# 1____DI_DO___v1_0.net
KiCad netlist of a schematic drawn in Altium Designer
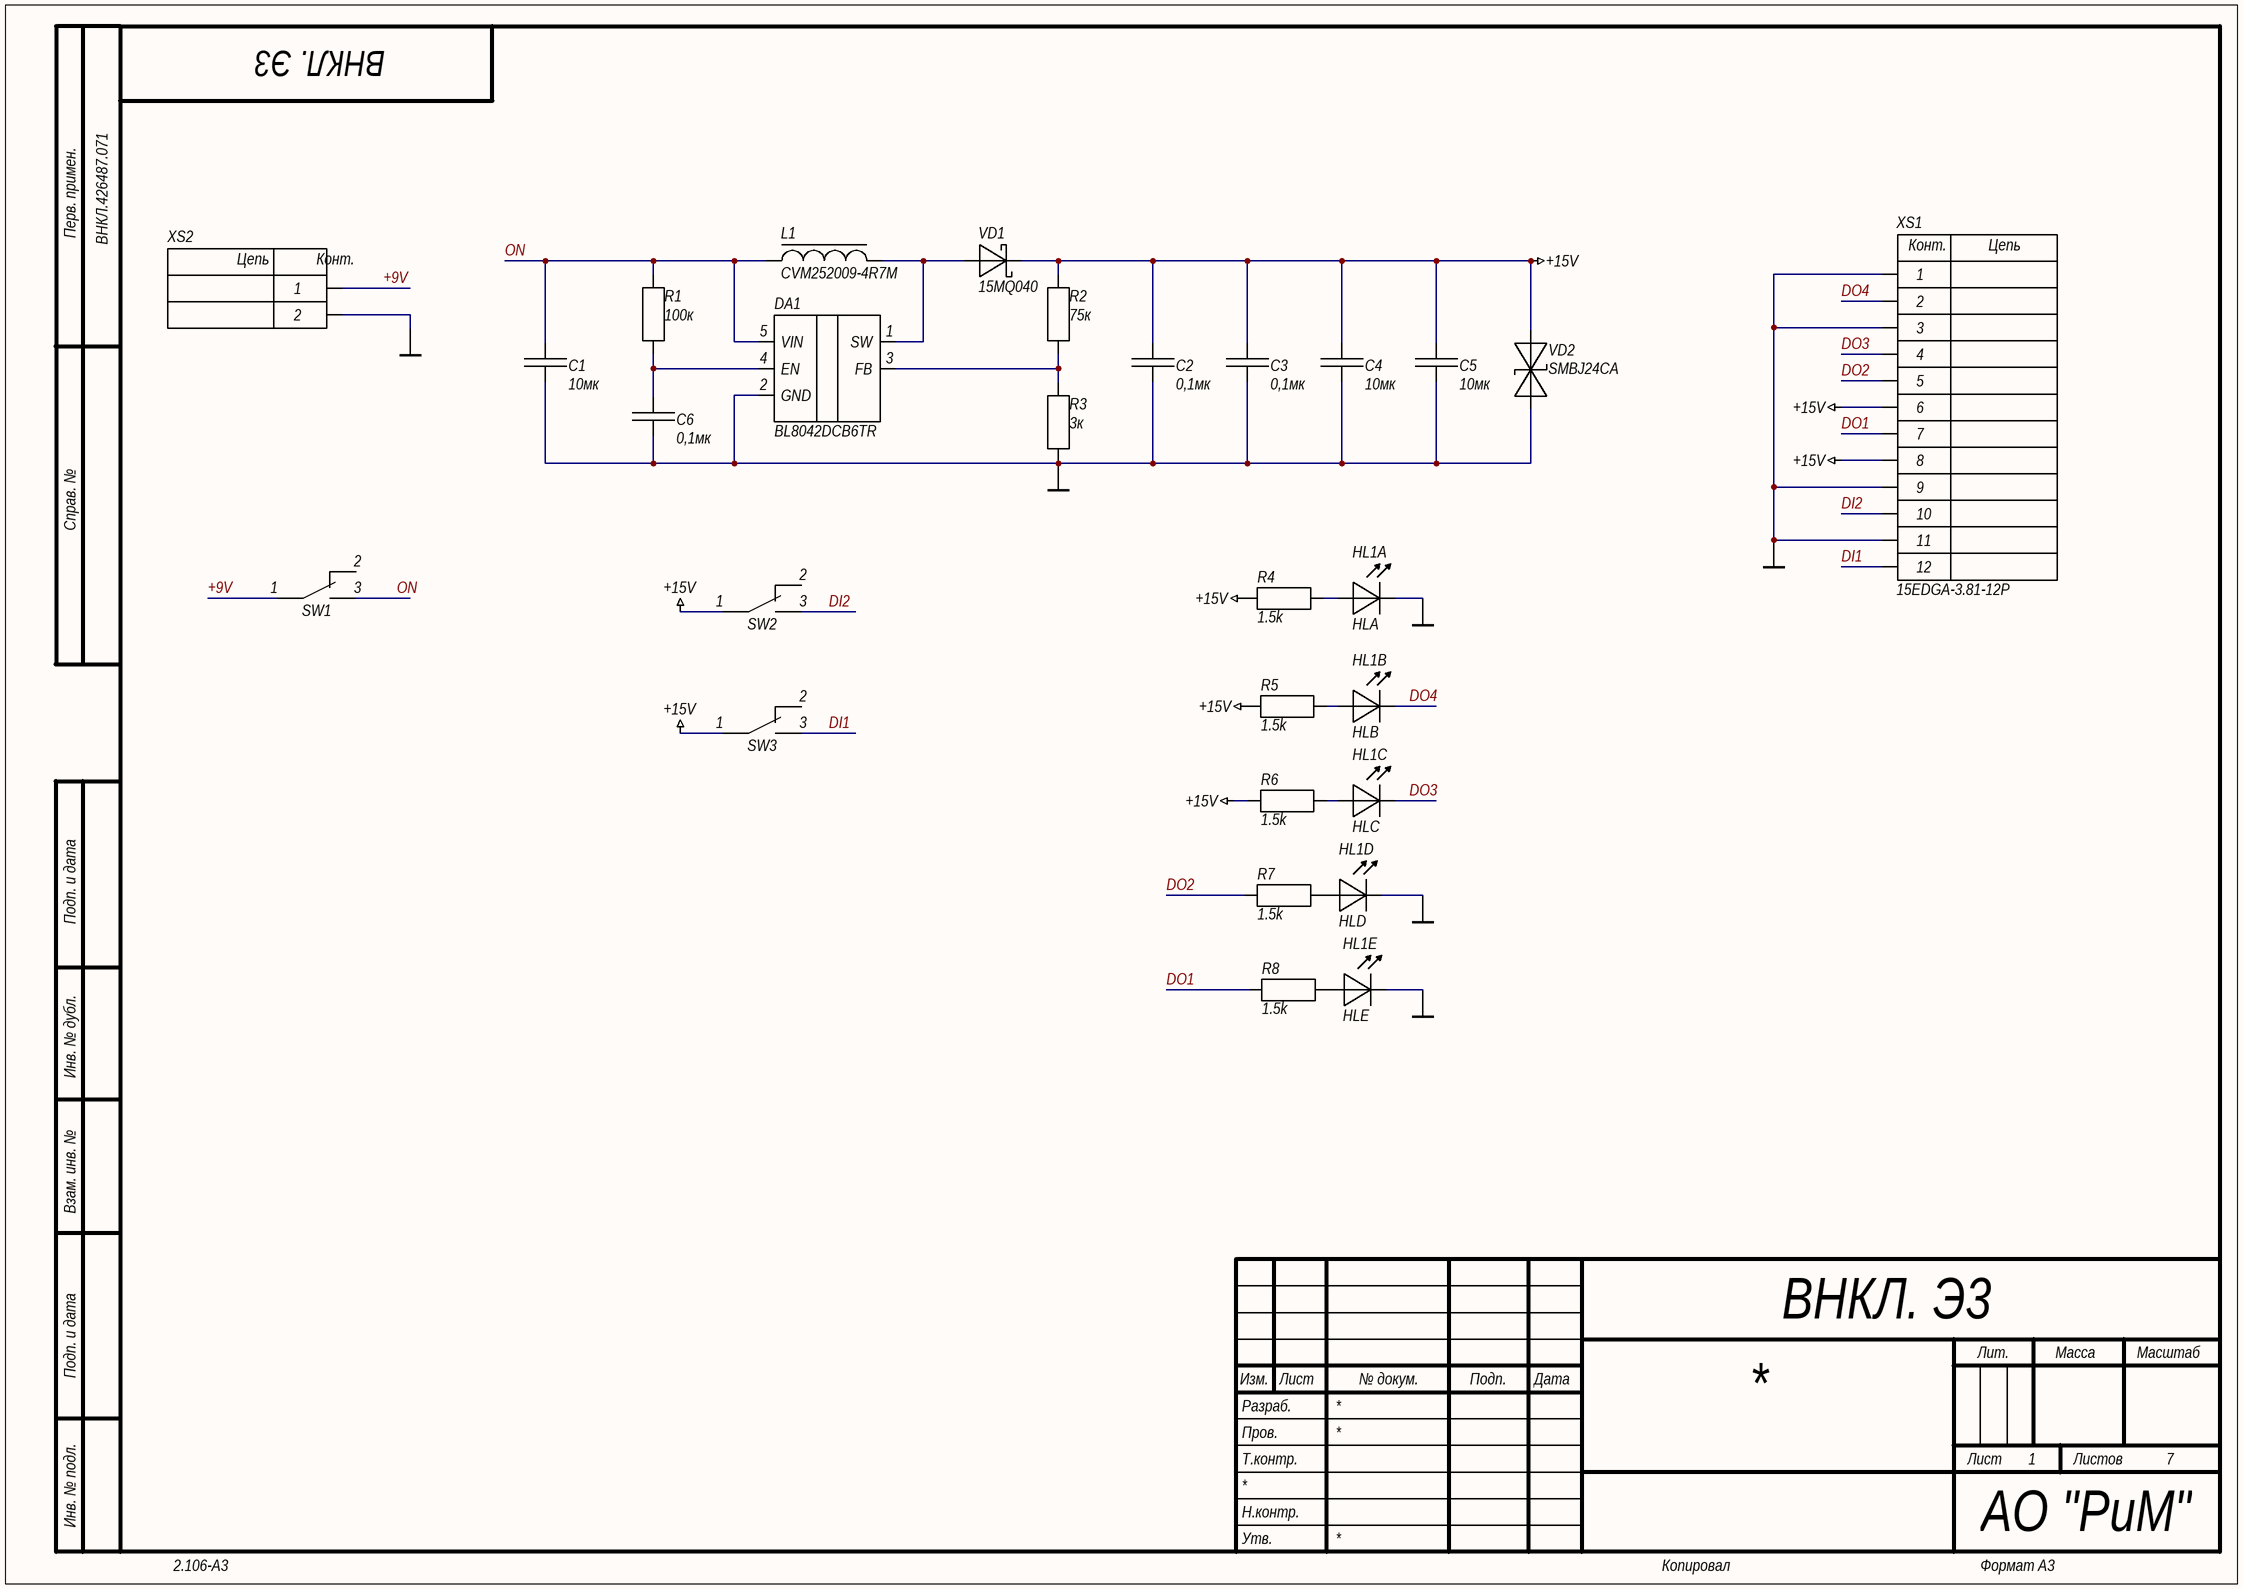
[diagram p0: 1.Устройство_Проверки_DI_DO_АКРОС_v1.0.SchDoc]

(export (version "E")
  (design (tool "Eeschema 10.0.6"))
  (components
    (comp (ref "C1")
      (value "10мк")
      (footprint "CAP: 0805")
      (libsource (lib "capacitor") (part "Ceramic_0805"))
    )
    (comp (ref "C2")
      (value "0,1мк")
      (footprint "CAP: 0402")
      (libsource (lib "capacitor") (part "Ceramic_0402"))
    )
    (comp (ref "C3")
      (value "0,1мк")
      (footprint "CAP: 0402")
      (libsource (lib "capacitor") (part "Ceramic_0402"))
    )
    (comp (ref "C4")
      (value "10мк")
      (footprint "CAP: 0805")
      (libsource (lib "capacitor") (part "Ceramic_0805"))
    )
    (comp (ref "C5")
      (value "10мк")
      (footprint "CAP: 0805")
      (libsource (lib "capacitor") (part "Ceramic_0805"))
    )
    (comp (ref "C6")
      (value "0,1мк")
      (footprint "CAP: 0402")
      (libsource (lib "capacitor") (part "Ceramic_0402"))
    )
    (comp (ref "DA1")
      (value "BL8042DCB6TR")
      (footprint "SOT23-6")
      (description "Boost converter")
      (libsource (lib "ic-power-supply") (part "BL8042DCB6TR"))
    )
    (comp (ref "HL1") (value "HLA") (footprint "L-914GDT") (libsource (lib "diode") (part "L-914GDT")))
    (comp (ref "L1")
      (value "CVM252009-4R7M")
      (footprint "IND: 1008")
      (libsource (lib "inductor") (part "CVM252009"))
    )
    (comp (ref "R1") (value "100к") (footprint "RES: 0402") (libsource (lib "") (part "Resistor_0402_1")))
    (comp (ref "R2") (value "75к") (footprint "RES: 0402") (libsource (lib "") (part "Resistor_0402_1")))
    (comp (ref "R3") (value "3к") (footprint "RES: 0402") (libsource (lib "") (part "Resistor_0402_1")))
    (comp (ref "R4")
      (value "1.5k")
      (footprint "RES: 0402")
      (libsource (lib "resistor") (part "Resistor_0402"))
    )
    (comp (ref "R5")
      (value "1.5k")
      (footprint "RES: 0402")
      (libsource (lib "resistor") (part "Resistor_0402"))
    )
    (comp (ref "R6")
      (value "1.5k")
      (footprint "RES: 0402")
      (libsource (lib "resistor") (part "Resistor_0402"))
    )
    (comp (ref "R7") (value "1.5k") (footprint "RES: 0402") (libsource (lib "") (part "Resistor_0402_2")))
    (comp (ref "R8") (value "1.5k") (footprint "RES: 0402") (libsource (lib "") (part "Resistor_0402_2")))
    (comp (ref "SW1")
      (value "Button-kcd11-102")
      (footprint "BUT: kcd11-102")
      (libsource (lib "electromechanics") (part "Button-kcd11-102"))
    )
    (comp (ref "SW2")
      (value "Button-kcd11-102")
      (footprint "BUT: kcd11-102")
      (libsource (lib "electromechanics") (part "Button-kcd11-102"))
    )
    (comp (ref "SW3")
      (value "Button-kcd11-102")
      (footprint "BUT: kcd11-102")
      (libsource (lib "electromechanics") (part "Button-kcd11-102"))
    )
    (comp (ref "VD1")
      (value "15MQ040")
      (footprint "DIODE: SMA")
      (libsource (lib "diode") (part "Schottky_single"))
    )
    (comp (ref "VD2")
      (value "SMBJ24CA")
      (footprint "DIODE: SMB")
      (libsource (lib "diode") (part "TVS_single"))
    )
    (comp (ref "XS1")
      (value "15EDGA-3.81-12P")
      (footprint "CON: 15EDGA-3.81-12P")
      (libsource (lib "connector") (part "CONNECTOR-12 - 3,81mm"))
    )
    (comp (ref "XS2")
      (value "XS?")
      (footprint "BAT: Krona")
      (libsource (lib "connector") (part "Connector_Krona"))
    )
  )
  (nets
    (net (code "1") (name "+15V") (class "Default")
      (node (ref "C2") (pin "1") (pinfunction "1_1") (pintype "passive"))
      (node (ref "C3") (pin "1") (pinfunction "1_1") (pintype "passive"))
      (node (ref "C4") (pin "1") (pinfunction "1_1") (pintype "passive"))
      (node (ref "C5") (pin "1") (pinfunction "1_1") (pintype "passive"))
      (node (ref "R2") (pin "2") (pinfunction "2_2") (pintype "passive"))
      (node (ref "R4") (pin "1") (pinfunction "1_1") (pintype "passive"))
      (node (ref "R5") (pin "1") (pinfunction "1_1") (pintype "passive"))
      (node (ref "R6") (pin "1") (pinfunction "1_1") (pintype "passive"))
      (node (ref "SW2") (pin "1") (pinfunction "1_1") (pintype "passive"))
      (node (ref "SW3") (pin "1") (pinfunction "1_1") (pintype "passive"))
      (node (ref "VD1") (pin "2") (pinfunction "2_2") (pintype "passive"))
      (node (ref "VD2") (pin "1") (pinfunction "A_1") (pintype "passive"))
      (node (ref "XS1") (pin "6") (pinfunction "6_6") (pintype "passive"))
      (node (ref "XS1") (pin "8") (pinfunction "8_8") (pintype "power_in"))
    )
    (net (code "2") (name "/+9V") (class "Default")
      (node (ref "SW1") (pin "1") (pinfunction "1_1") (pintype "passive"))
      (node (ref "XS2") (pin "1") (pinfunction "1_1") (pintype "passive"))
    )
    (net (code "3") (name "/DI1") (class "Default")
      (node (ref "SW3") (pin "3") (pinfunction "3_3") (pintype "passive"))
      (node (ref "XS1") (pin "12") (pinfunction "12_12") (pintype "power_in"))
    )
    (net (code "4") (name "/DI2") (class "Default")
      (node (ref "SW2") (pin "3") (pinfunction "3_3") (pintype "passive"))
      (node (ref "XS1") (pin "10") (pinfunction "10_10") (pintype "passive"))
    )
    (net (code "5") (name "/DO1") (class "Default")
      (node (ref "R8") (pin "2") (pinfunction "2_2") (pintype "passive"))
      (node (ref "XS1") (pin "7") (pinfunction "7_7") (pintype "power_in"))
    )
    (net (code "6") (name "/DO2") (class "Default")
      (node (ref "R7") (pin "2") (pinfunction "2_2") (pintype "passive"))
      (node (ref "XS1") (pin "5") (pinfunction "5_5") (pintype "passive"))
    )
    (net (code "7") (name "/DO3") (class "Default")
      (node (ref "HL1") (pin "5") (pinfunction "C_5") (pintype "passive"))
      (node (ref "XS1") (pin "4") (pinfunction "4_4") (pintype "power_in"))
    )
    (net (code "8") (name "/DO4") (class "Default")
      (node (ref "HL1") (pin "3") (pinfunction "C_3") (pintype "passive"))
      (node (ref "XS1") (pin "2") (pinfunction "2_2") (pintype "passive"))
    )
    (net (code "9") (name "/ON") (class "Default")
      (node (ref "C1") (pin "1") (pinfunction "1_1") (pintype "passive"))
      (node (ref "DA1") (pin "5") (pinfunction "VIN_5") (pintype "open_emitter"))
      (node (ref "L1") (pin "2") (pinfunction "2_2") (pintype "passive"))
      (node (ref "R1") (pin "2") (pinfunction "2_2") (pintype "passive"))
      (node (ref "SW1") (pin "3") (pinfunction "3_3") (pintype "passive"))
    )
    (net (code "10") (name "GND") (class "Default")
      (node (ref "C1") (pin "2") (pinfunction "2_2") (pintype "passive"))
      (node (ref "C2") (pin "2") (pinfunction "2_2") (pintype "passive"))
      (node (ref "C3") (pin "2") (pinfunction "2_2") (pintype "passive"))
      (node (ref "C4") (pin "2") (pinfunction "2_2") (pintype "passive"))
      (node (ref "C5") (pin "2") (pinfunction "2_2") (pintype "passive"))
      (node (ref "C6") (pin "2") (pinfunction "2_2") (pintype "passive"))
      (node (ref "DA1") (pin "2") (pinfunction "GND_2") (pintype "power_in"))
      (node (ref "HL1") (pin "1") (pinfunction "C_1") (pintype "passive"))
      (node (ref "HL1") (pin "7") (pinfunction "C_7") (pintype "passive"))
      (node (ref "HL1") (pin "9") (pinfunction "C_9") (pintype "passive"))
      (node (ref "R3") (pin "1") (pinfunction "1_1") (pintype "passive"))
      (node (ref "VD2") (pin "2") (pinfunction "C_2") (pintype "passive"))
      (node (ref "XS1") (pin "1") (pinfunction "1_1") (pintype "passive"))
      (node (ref "XS1") (pin "11") (pinfunction "11_11") (pintype "power_in"))
      (node (ref "XS1") (pin "3") (pinfunction "3_3") (pintype "power_in"))
      (node (ref "XS1") (pin "9") (pinfunction "9_9") (pintype "passive"))
      (node (ref "XS2") (pin "2") (pinfunction "2_2") (pintype "passive"))
    )
    (net (code "11") (name "Net-(DA1-EN)") (class "Default")
      (node (ref "C6") (pin "1") (pinfunction "1_1") (pintype "passive"))
      (node (ref "DA1") (pin "4") (pinfunction "EN_4") (pintype "passive"))
      (node (ref "R1") (pin "1") (pinfunction "1_1") (pintype "passive"))
    )
    (net (code "12") (name "Net-(DA1-FB)") (class "Default")
      (node (ref "DA1") (pin "3") (pinfunction "FB_3") (pintype "passive"))
      (node (ref "R2") (pin "1") (pinfunction "1_1") (pintype "passive"))
      (node (ref "R3") (pin "2") (pinfunction "2_2") (pintype "passive"))
    )
    (net (code "13") (name "Net-(DA1-SW)") (class "Default")
      (node (ref "DA1") (pin "1") (pinfunction "SW_1") (pintype "passive"))
      (node (ref "L1") (pin "1") (pinfunction "1_1") (pintype "passive"))
      (node (ref "VD1") (pin "1") (pinfunction "1_1") (pintype "passive"))
    )
    (net (code "14") (name "Net-(HL1A-A)") (class "Default")
      (node (ref "HL1") (pin "2") (pinfunction "A_2") (pintype "passive"))
      (node (ref "R4") (pin "2") (pinfunction "2_2") (pintype "passive"))
    )
    (net (code "15") (name "Net-(HL1B-A)") (class "Default")
      (node (ref "HL1") (pin "4") (pinfunction "A_4") (pintype "passive"))
      (node (ref "R5") (pin "2") (pinfunction "2_2") (pintype "passive"))
    )
    (net (code "16") (name "Net-(HL1C-A)") (class "Default")
      (node (ref "HL1") (pin "6") (pinfunction "A_6") (pintype "passive"))
      (node (ref "R6") (pin "2") (pinfunction "2_2") (pintype "passive"))
    )
    (net (code "17") (name "Net-(HL1D-A)") (class "Default")
      (node (ref "HL1") (pin "8") (pinfunction "A_8") (pintype "passive"))
      (node (ref "R7") (pin "1") (pinfunction "1_1") (pintype "passive"))
    )
    (net (code "18") (name "Net-(HL1E-A)") (class "Default")
      (node (ref "HL1") (pin "10") (pinfunction "A_10") (pintype "passive"))
      (node (ref "R8") (pin "1") (pinfunction "1_1") (pintype "passive"))
    )
    (net (code "19") (name "unconnected-(SW1-Pad2)") (class "Default")
      (node (ref "SW1") (pin "2") (pinfunction "2_2") (pintype "passive"))
    )
    (net (code "20") (name "unconnected-(SW2-Pad2)") (class "Default")
      (node (ref "SW2") (pin "2") (pinfunction "2_2") (pintype "passive"))
    )
    (net (code "21") (name "unconnected-(SW3-Pad2)") (class "Default")
      (node (ref "SW3") (pin "2") (pinfunction "2_2") (pintype "passive"))
    )
  )
)
